# MCU-Debug.net
KiCad netlist of a schematic drawn in Altium Designer
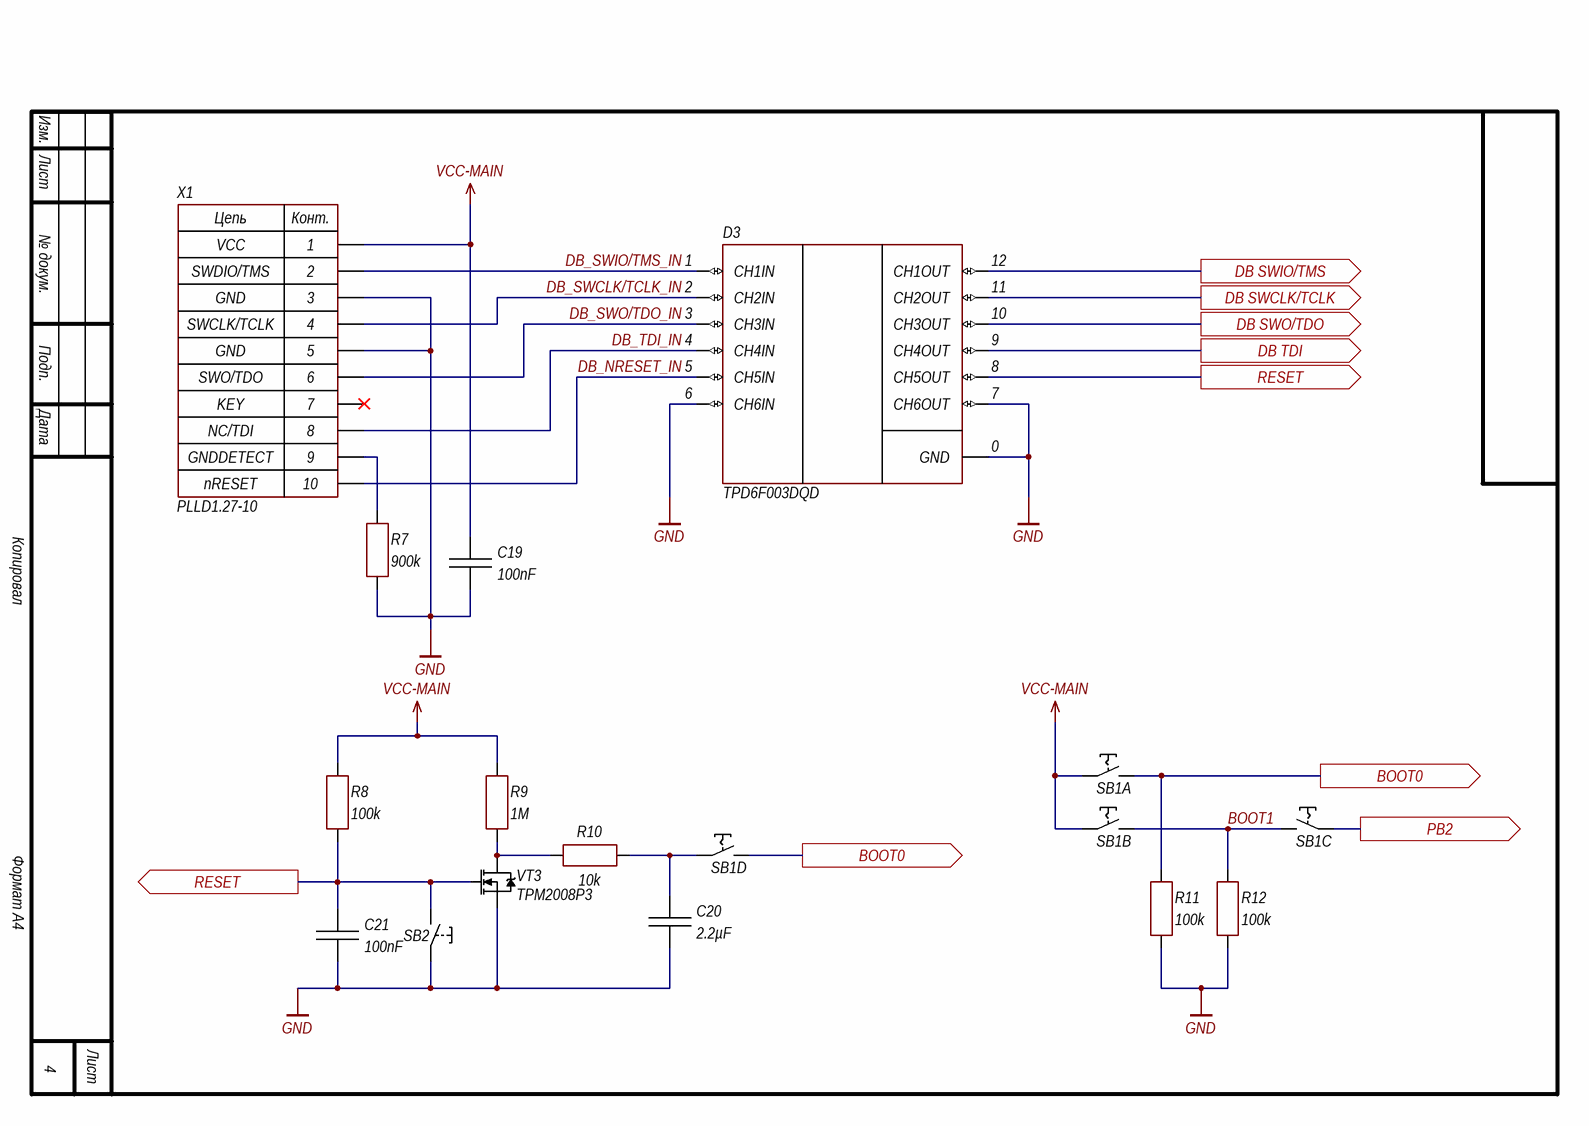
[diagram p0: MCU-Debug.SchDoc]

(export (version "E")
  (design (tool "Eeschema 10.0.6"))
  (components
    (comp (ref "C19") (value "100nF") (footprint "CH0402C") (libsource (lib "Discrete") (part "Capacitor")))
    (comp (ref "C20") (value "2.2µF") (footprint "CH0402C") (libsource (lib "Discrete") (part "Capacitor")))
    (comp (ref "C21") (value "100nF") (footprint "CH0402C") (libsource (lib "Discrete") (part "Capacitor")))
    (comp (ref "D3")
      (value "TPD6F003DQD")
      (footprint "12-WSON (2.5x1.35 mm)")
      (description "6-bit IO protection")
      (fields (field (name "MANUFACTURER") "Texas Instruments"))
      (libsource (lib "Analog") (part "TPD6F003"))
    )
    (comp (ref "R7") (value "900k") (footprint "CH0402R") (libsource (lib "Discrete") (part "Resistor")))
    (comp (ref "R8") (value "100k") (footprint "CH0402R") (libsource (lib "Discrete") (part "Resistor")))
    (comp (ref "R9") (value "1M") (footprint "CH0402R") (libsource (lib "Discrete") (part "Resistor")))
    (comp (ref "R10") (value "10k") (footprint "CH0402R") (libsource (lib "") (part "Resistor_1")))
    (comp (ref "R11") (value "100k") (footprint "CH0402R") (libsource (lib "Discrete") (part "Resistor")))
    (comp (ref "R12") (value "100k") (footprint "CH0402R") (libsource (lib "Discrete") (part "Resistor")))
    (comp (ref "SB1")
      (value "*")
      (footprint "BUT: DSHP04TS")
      (description "4 Array, latching")
      (libsource (lib "Connectors") (part "4(1)-Switch"))
    )
    (comp (ref "SB2")
      (value "\"Кнопка\"")
      (footprint "BUT: YTS-A017")
      (description "Button, no latching")
      (libsource (lib "Connectors") (part "1-Button"))
    )
    (comp (ref "VT3")
      (value "TPM2008P3")
      (footprint "DFN1006-3L")
      (description "Mosfet")
      (fields (field (name "MANUFACTURER") "TECH PUBLIC"))
      (libsource (lib "Transistor") (part "N-chanel"))
    )
    (comp (ref "X1")
      (value "PLLD1.27-10")
      (footprint "CON: PLLD-1.27-10")
      (libsource (lib "Connectors") (part "10-Connector"))
    )
  )
  (nets
    (net (code "1") (name "/BOOT0") (class "Default")
      (node (ref "R11") (pin "2") (pinfunction "2_2") (pintype "passive"))
      (node (ref "SB1") (pin "5") (pinfunction "5_5") (pintype "passive"))
      (node (ref "SB1") (pin "8") (pinfunction "8_8") (pintype "passive"))
    )
    (net (code "2") (name "/BOOT1") (class "Default")
      (node (ref "R12") (pin "2") (pinfunction "2_2") (pintype "passive"))
      (node (ref "SB1") (pin "6") (pinfunction "6_6") (pintype "passive"))
      (node (ref "SB1") (pin "7") (pinfunction "7_7") (pintype "passive"))
    )
    (net (code "3") (name "/DB SWCLK{slash}TCLK") (class "Default")
      (node (ref "D3") (pin "11") (pinfunction "CH2OUT_11") (pintype "bidirectional"))
    )
    (net (code "4") (name "/DB SWIO{slash}TMS") (class "Default")
      (node (ref "D3") (pin "12") (pinfunction "CH1OUT_12") (pintype "bidirectional"))
    )
    (net (code "5") (name "/DB SWO{slash}TDO") (class "Default")
      (node (ref "D3") (pin "10") (pinfunction "CH3OUT_10") (pintype "bidirectional"))
    )
    (net (code "6") (name "/DB TDI") (class "Default")
      (node (ref "D3") (pin "9") (pinfunction "CH4OUT_9") (pintype "bidirectional"))
    )
    (net (code "7") (name "/DB_NRESET_IN") (class "Default")
      (node (ref "D3") (pin "5") (pinfunction "CH5IN_5") (pintype "bidirectional"))
      (node (ref "X1") (pin "10") (pinfunction "10_10") (pintype "passive"))
    )
    (net (code "8") (name "/DB_SWCLK{slash}TCLK_IN") (class "Default")
      (node (ref "D3") (pin "2") (pinfunction "CH2IN_2") (pintype "bidirectional"))
      (node (ref "X1") (pin "4") (pinfunction "4_4") (pintype "passive"))
    )
    (net (code "9") (name "/DB_SWIO{slash}TMS_IN") (class "Default")
      (node (ref "D3") (pin "1") (pinfunction "CH1IN_1") (pintype "bidirectional"))
      (node (ref "X1") (pin "2") (pinfunction "2_2") (pintype "passive"))
    )
    (net (code "10") (name "/DB_SWO{slash}TDO_IN") (class "Default")
      (node (ref "D3") (pin "3") (pinfunction "CH3IN_3") (pintype "bidirectional"))
      (node (ref "X1") (pin "6") (pinfunction "6_6") (pintype "passive"))
    )
    (net (code "11") (name "/DB_TDI_IN") (class "Default")
      (node (ref "D3") (pin "4") (pinfunction "CH4IN_4") (pintype "bidirectional"))
      (node (ref "X1") (pin "8") (pinfunction "8_8") (pintype "passive"))
    )
    (net (code "12") (name "/PB2") (class "Default")
      (node (ref "SB1") (pin "3") (pinfunction "3_3") (pintype "passive"))
    )
    (net (code "13") (name "/RESET") (class "Default")
      (node (ref "C21") (pin "2") (pinfunction "2_2") (pintype "passive"))
      (node (ref "D3") (pin "8") (pinfunction "CH5OUT_8") (pintype "bidirectional"))
      (node (ref "R8") (pin "1") (pinfunction "1_1") (pintype "passive"))
      (node (ref "SB2") (pin "2") (pinfunction "2_2") (pintype "passive"))
      (node (ref "VT3") (pin "1") (pinfunction "G_1") (pintype "passive"))
    )
    (net (code "14") (name "GND") (class "Default")
      (node (ref "C19") (pin "1") (pinfunction "1_1") (pintype "passive"))
      (node (ref "C20") (pin "1") (pinfunction "1_1") (pintype "passive"))
      (node (ref "C21") (pin "1") (pinfunction "1_1") (pintype "passive"))
      (node (ref "D3") (pin "0") (pinfunction "GND_0") (pintype "power_in"))
      (node (ref "D3") (pin "6") (pinfunction "CH6IN_6") (pintype "bidirectional"))
      (node (ref "D3") (pin "7") (pinfunction "CH6OUT_7") (pintype "bidirectional"))
      (node (ref "R11") (pin "1") (pinfunction "1_1") (pintype "passive"))
      (node (ref "R12") (pin "1") (pinfunction "1_1") (pintype "passive"))
      (node (ref "R7") (pin "1") (pinfunction "1_1") (pintype "passive"))
      (node (ref "SB2") (pin "1") (pinfunction "1_1") (pintype "passive"))
      (node (ref "VT3") (pin "3") (pinfunction "S_3") (pintype "passive"))
      (node (ref "X1") (pin "3") (pinfunction "3_3") (pintype "passive"))
      (node (ref "X1") (pin "5") (pinfunction "5_5") (pintype "passive"))
    )
    (net (code "15") (name "Net-(C20-Pad2)") (class "Default")
      (node (ref "C20") (pin "2") (pinfunction "2_2") (pintype "passive"))
      (node (ref "R10") (pin "2") (pinfunction "2_2") (pintype "passive"))
      (node (ref "SB1") (pin "4") (pinfunction "4_4") (pintype "passive"))
    )
    (net (code "16") (name "Net-(R7-Pad2)") (class "Default")
      (node (ref "R7") (pin "2") (pinfunction "2_2") (pintype "passive"))
      (node (ref "X1") (pin "9") (pinfunction "9_9") (pintype "passive"))
    )
    (net (code "17") (name "Net-(VT3-D)") (class "Default")
      (node (ref "R10") (pin "1") (pinfunction "1_1") (pintype "passive"))
      (node (ref "R9") (pin "1") (pinfunction "1_1") (pintype "passive"))
      (node (ref "VT3") (pin "2") (pinfunction "D_2") (pintype "passive"))
    )
    (net (code "18") (name "VCC-MAIN") (class "Default")
      (node (ref "C19") (pin "2") (pinfunction "2_2") (pintype "passive"))
      (node (ref "R8") (pin "2") (pinfunction "2_2") (pintype "passive"))
      (node (ref "R9") (pin "2") (pinfunction "2_2") (pintype "passive"))
      (node (ref "SB1") (pin "1") (pinfunction "1_1") (pintype "passive"))
      (node (ref "SB1") (pin "2") (pinfunction "2_2") (pintype "passive"))
      (node (ref "X1") (pin "1") (pinfunction "1_1") (pintype "passive"))
    )
    (net (code "19") (name "unconnected-(X1-Pad7)") (class "Default")
      (node (ref "X1") (pin "7") (pinfunction "7_7") (pintype "passive+no_connect"))
    )
  )
)
